# Sensors.net
KiCad netlist of a schematic drawn in Altium Designer
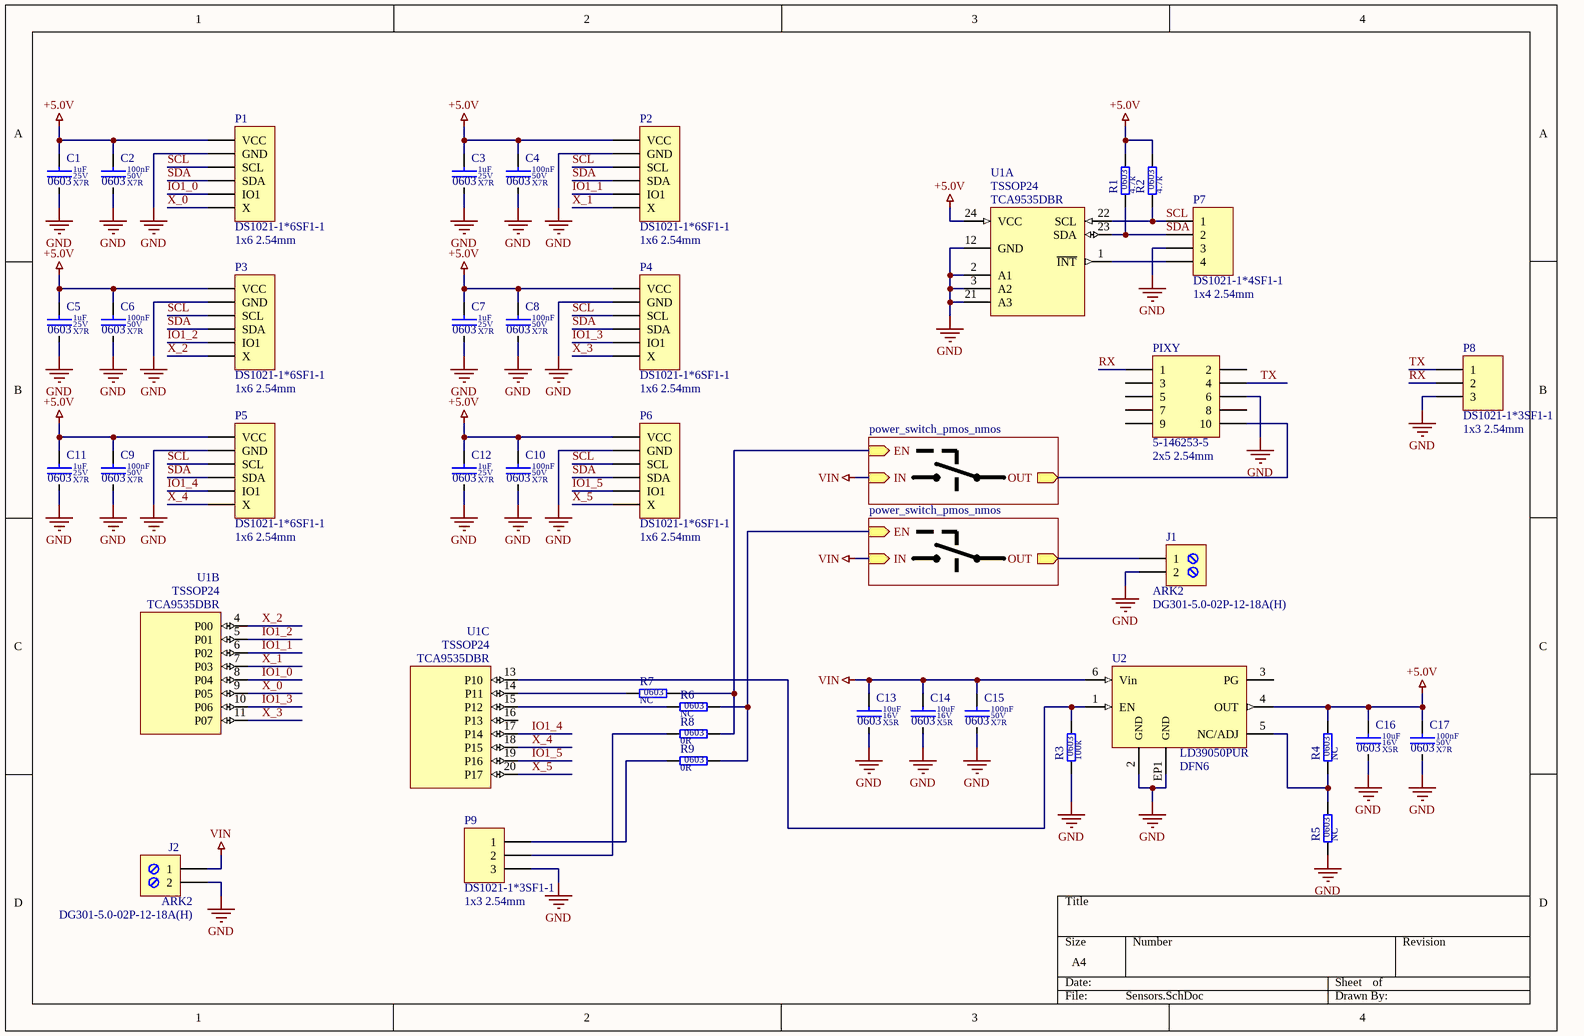
[diagram p0: Sensors.SchDoc]

(export (version "E")
  (design (tool "Eeschema 10.0.6"))
  (components
    (comp (ref "C1")
      (value "1uF")
      (footprint "C_0603_1608")
      (description "Capacitor")
      (fields
        (field (name "DIELECTRIC") "X7R")
        (field (name "VOLTAGE") "25V")
        (field (name "SCH_FOOTPRINT") "0603")
        (field (name "PART NUMBER") "C_1uF_25V_X7R_0603_10")
        (field (name "MANUFACTURER") "Samsung")
      )
      (libsource (lib "Library") (part "C"))
    )
    (comp (ref "C2")
      (value "100nF")
      (footprint "C_0603_1608")
      (description "Capacitor")
      (fields
        (field (name "DIELECTRIC") "X7R")
        (field (name "VOLTAGE") "50V")
        (field (name "SCH_FOOTPRINT") "0603")
        (field (name "PART NUMBER") "C_100nF_50V_X7R_0603_5")
        (field (name "MANUFACTURER") "Samsung")
      )
      (libsource (lib "Library") (part "C"))
    )
    (comp (ref "C3")
      (value "1uF")
      (footprint "C_0603_1608")
      (description "Capacitor")
      (fields
        (field (name "DIELECTRIC") "X7R")
        (field (name "VOLTAGE") "25V")
        (field (name "SCH_FOOTPRINT") "0603")
        (field (name "PART NUMBER") "C_1uF_25V_X7R_0603_10")
        (field (name "MANUFACTURER") "Samsung")
      )
      (libsource (lib "Library") (part "C"))
    )
    (comp (ref "C4")
      (value "100nF")
      (footprint "C_0603_1608")
      (description "Capacitor")
      (fields
        (field (name "DIELECTRIC") "X7R")
        (field (name "VOLTAGE") "50V")
        (field (name "SCH_FOOTPRINT") "0603")
        (field (name "PART NUMBER") "C_100nF_50V_X7R_0603_5")
        (field (name "MANUFACTURER") "Samsung")
      )
      (libsource (lib "Library") (part "C"))
    )
    (comp (ref "C5")
      (value "1uF")
      (footprint "C_0603_1608")
      (description "Capacitor")
      (fields
        (field (name "DIELECTRIC") "X7R")
        (field (name "VOLTAGE") "25V")
        (field (name "SCH_FOOTPRINT") "0603")
        (field (name "PART NUMBER") "C_1uF_25V_X7R_0603_10")
        (field (name "MANUFACTURER") "Samsung")
      )
      (libsource (lib "Library") (part "C"))
    )
    (comp (ref "C6")
      (value "100nF")
      (footprint "C_0603_1608")
      (description "Capacitor")
      (fields
        (field (name "DIELECTRIC") "X7R")
        (field (name "VOLTAGE") "50V")
        (field (name "SCH_FOOTPRINT") "0603")
        (field (name "PART NUMBER") "C_100nF_50V_X7R_0603_5")
        (field (name "MANUFACTURER") "Samsung")
      )
      (libsource (lib "Library") (part "C"))
    )
    (comp (ref "C7")
      (value "1uF")
      (footprint "C_0603_1608")
      (description "Capacitor")
      (fields
        (field (name "DIELECTRIC") "X7R")
        (field (name "VOLTAGE") "25V")
        (field (name "SCH_FOOTPRINT") "0603")
        (field (name "PART NUMBER") "C_1uF_25V_X7R_0603_10")
        (field (name "MANUFACTURER") "Samsung")
      )
      (libsource (lib "Library") (part "C"))
    )
    (comp (ref "C8")
      (value "100nF")
      (footprint "C_0603_1608")
      (description "Capacitor")
      (fields
        (field (name "DIELECTRIC") "X7R")
        (field (name "VOLTAGE") "50V")
        (field (name "SCH_FOOTPRINT") "0603")
        (field (name "PART NUMBER") "C_100nF_50V_X7R_0603_5")
        (field (name "MANUFACTURER") "Samsung")
      )
      (libsource (lib "Library") (part "C"))
    )
    (comp (ref "C9")
      (value "100nF")
      (footprint "C_0603_1608")
      (description "Capacitor")
      (fields
        (field (name "DIELECTRIC") "X7R")
        (field (name "VOLTAGE") "50V")
        (field (name "SCH_FOOTPRINT") "0603")
        (field (name "PART NUMBER") "C_100nF_50V_X7R_0603_5")
        (field (name "MANUFACTURER") "Samsung")
      )
      (libsource (lib "Library") (part "C"))
    )
    (comp (ref "C10")
      (value "100nF")
      (footprint "C_0603_1608")
      (description "Capacitor")
      (fields
        (field (name "DIELECTRIC") "X7R")
        (field (name "VOLTAGE") "50V")
        (field (name "SCH_FOOTPRINT") "0603")
        (field (name "PART NUMBER") "C_100nF_50V_X7R_0603_5")
        (field (name "MANUFACTURER") "Samsung")
      )
      (libsource (lib "Library") (part "C"))
    )
    (comp (ref "C11")
      (value "1uF")
      (footprint "C_0603_1608")
      (description "Capacitor")
      (fields
        (field (name "DIELECTRIC") "X7R")
        (field (name "VOLTAGE") "25V")
        (field (name "SCH_FOOTPRINT") "0603")
        (field (name "PART NUMBER") "C_1uF_25V_X7R_0603_10")
        (field (name "MANUFACTURER") "Samsung")
      )
      (libsource (lib "Library") (part "C"))
    )
    (comp (ref "C12")
      (value "1uF")
      (footprint "C_0603_1608")
      (description "Capacitor")
      (fields
        (field (name "DIELECTRIC") "X7R")
        (field (name "VOLTAGE") "25V")
        (field (name "SCH_FOOTPRINT") "0603")
        (field (name "PART NUMBER") "C_1uF_25V_X7R_0603_10")
        (field (name "MANUFACTURER") "Samsung")
      )
      (libsource (lib "Library") (part "C"))
    )
    (comp (ref "C13")
      (value "10uF")
      (footprint "C_0603_1608")
      (description "Capacitor")
      (fields
        (field (name "DIELECTRIC") "X5R")
        (field (name "VOLTAGE") "16V")
        (field (name "SCH_FOOTPRINT") "0603")
        (field (name "PART NUMBER") "C_10uF_16V_X5R_0603_20")
        (field (name "MANUFACTURER") "Samsung Electro-Mechanics")
      )
      (libsource (lib "Library") (part "C"))
    )
    (comp (ref "C14")
      (value "10uF")
      (footprint "C_0603_1608")
      (description "Capacitor")
      (fields
        (field (name "DIELECTRIC") "X5R")
        (field (name "VOLTAGE") "16V")
        (field (name "SCH_FOOTPRINT") "0603")
        (field (name "PART NUMBER") "C_10uF_16V_X5R_0603_20")
        (field (name "MANUFACTURER") "Samsung Electro-Mechanics")
      )
      (libsource (lib "Library") (part "C"))
    )
    (comp (ref "C15")
      (value "100nF")
      (footprint "C_0603_1608")
      (description "Capacitor")
      (fields
        (field (name "DIELECTRIC") "X7R")
        (field (name "VOLTAGE") "50V")
        (field (name "SCH_FOOTPRINT") "0603")
        (field (name "PART NUMBER") "C_100nF_50V_X7R_0603_5")
        (field (name "MANUFACTURER") "Samsung")
      )
      (libsource (lib "Library") (part "C"))
    )
    (comp (ref "C16")
      (value "10uF")
      (footprint "C_0603_1608")
      (description "Capacitor")
      (fields
        (field (name "DIELECTRIC") "X5R")
        (field (name "VOLTAGE") "16V")
        (field (name "SCH_FOOTPRINT") "0603")
        (field (name "PART NUMBER") "C_10uF_16V_X5R_0603_20")
        (field (name "MANUFACTURER") "Samsung Electro-Mechanics")
      )
      (libsource (lib "Library") (part "C"))
    )
    (comp (ref "C17")
      (value "100nF")
      (footprint "C_0603_1608")
      (description "Capacitor")
      (fields
        (field (name "DIELECTRIC") "X7R")
        (field (name "VOLTAGE") "50V")
        (field (name "SCH_FOOTPRINT") "0603")
        (field (name "PART NUMBER") "C_100nF_50V_X7R_0603_5")
        (field (name "MANUFACTURER") "Samsung")
      )
      (libsource (lib "Library") (part "C"))
    )
    (comp (ref "J1")
      (value "DG301-5.0-02P-12-18A(H)")
      (footprint "J_ARK2")
      (description "ARK Screw terminal, 2-Pin")
      (fields
        (field (name "SCH_FOOTPRINT") "ARK2")
        (field (name "PART NUMBER") "J_TB-5.0-P-2P")
        (field (name "MANUFACTURER") "DEGSON ELECTRONICS")
      )
      (libsource (lib "") (part "J_ARK2_1"))
    )
    (comp (ref "J2")
      (value "DG301-5.0-02P-12-18A(H)")
      (footprint "J_ARK2")
      (description "ARK Screw terminal, 2-Pin")
      (fields
        (field (name "SCH_FOOTPRINT") "ARK2")
        (field (name "PART NUMBER") "J_TB-5.0-P-2P")
        (field (name "MANUFACTURER") "DEGSON ELECTRONICS")
      )
      (libsource (lib "Library") (part "J_ARK2"))
    )
    (comp (ref "P1")
      (value "DS1021-1*6SF1-1")
      (footprint "P_HEADER_1x6_2.54")
      (description "Header, 6-Pin")
      (fields
        (field (name "PART NUMBER") "P_HEADER_1x6_2.54")
        (field (name "SCH_FOOTPRINT") "1x6 2.54mm")
        (field (name "MANUFACTURER") "Connfly")
      )
      (libsource (lib "Library") (part "P_HEADER_1x6"))
    )
    (comp (ref "P2")
      (value "DS1021-1*6SF1-1")
      (footprint "P_HEADER_1x6_2.54")
      (description "Header, 6-Pin")
      (fields
        (field (name "PART NUMBER") "P_HEADER_1x6_2.54")
        (field (name "SCH_FOOTPRINT") "1x6 2.54mm")
        (field (name "MANUFACTURER") "Connfly")
      )
      (libsource (lib "Library") (part "P_HEADER_1x6"))
    )
    (comp (ref "P3")
      (value "DS1021-1*6SF1-1")
      (footprint "P_HEADER_1x6_2.54")
      (description "Header, 6-Pin")
      (fields
        (field (name "PART NUMBER") "P_HEADER_1x6_2.54")
        (field (name "SCH_FOOTPRINT") "1x6 2.54mm")
        (field (name "MANUFACTURER") "Connfly")
      )
      (libsource (lib "Library") (part "P_HEADER_1x6"))
    )
    (comp (ref "P4")
      (value "DS1021-1*6SF1-1")
      (footprint "P_HEADER_1x6_2.54")
      (description "Header, 6-Pin")
      (fields
        (field (name "PART NUMBER") "P_HEADER_1x6_2.54")
        (field (name "SCH_FOOTPRINT") "1x6 2.54mm")
        (field (name "MANUFACTURER") "Connfly")
      )
      (libsource (lib "Library") (part "P_HEADER_1x6"))
    )
    (comp (ref "P5")
      (value "DS1021-1*6SF1-1")
      (footprint "P_HEADER_1x6_2.54")
      (description "Header, 6-Pin")
      (fields
        (field (name "PART NUMBER") "P_HEADER_1x6_2.54")
        (field (name "SCH_FOOTPRINT") "1x6 2.54mm")
        (field (name "MANUFACTURER") "Connfly")
      )
      (libsource (lib "Library") (part "P_HEADER_1x6"))
    )
    (comp (ref "P6")
      (value "DS1021-1*6SF1-1")
      (footprint "P_HEADER_1x6_2.54")
      (description "Header, 6-Pin")
      (fields
        (field (name "PART NUMBER") "P_HEADER_1x6_2.54")
        (field (name "SCH_FOOTPRINT") "1x6 2.54mm")
        (field (name "MANUFACTURER") "Connfly")
      )
      (libsource (lib "Library") (part "P_HEADER_1x6"))
    )
    (comp (ref "P7")
      (value "DS1021-1*4SF1-1")
      (footprint "P_HEADER_1x4_2.54")
      (description "Header, 4-Pin")
      (fields
        (field (name "PART NUMBER") "P_HEADER_1x4_2.54")
        (field (name "SCH_FOOTPRINT") "1x4 2.54mm")
        (field (name "MANUFACTURER") "Connfly")
      )
      (libsource (lib "Library") (part "P_HEADER_1x4"))
    )
    (comp (ref "P8")
      (value "DS1021-1*3SF1-1")
      (footprint "P_HEADER_1x3_2.54")
      (description "Header, 3-Pin")
      (fields
        (field (name "PART NUMBER") "P_HEADER_1x3_2.54")
        (field (name "SCH_FOOTPRINT") "1x3 2.54mm")
        (field (name "MANUFACTURER") "Connfly")
      )
      (libsource (lib "") (part "P_HEADER_1x3_1"))
    )
    (comp (ref "P9")
      (value "DS1021-1*3SF1-1")
      (footprint "P_HEADER_1x3_2.54")
      (description "Header, 3-Pin")
      (fields
        (field (name "PART NUMBER") "P_HEADER_1x3_2.54")
        (field (name "SCH_FOOTPRINT") "1x3 2.54mm")
        (field (name "MANUFACTURER") "Connfly")
      )
      (libsource (lib "Library") (part "P_HEADER_1x3"))
    )
    (comp (ref "PIXY")
      (value "5-146253-5")
      (footprint "P_HEADER_2x5_2.54")
      (description "Header, 10-Pin, Dual row")
      (fields
        (field (name "PART NUMBER") "P_HEADER_2x5_2.54")
        (field (name "SCH_FOOTPRINT") "2x5 2.54mm")
        (field (name "MANUFACTURER") "TE Connectivity")
      )
      (libsource (lib "Library") (part "P_HEADER_2x5"))
    )
    (comp (ref "R1")
      (value "4.7k")
      (footprint "R_0603_1608")
      (fields
        (field (name "SCH_FOOTPRINT") "0603")
        (field (name "PART NUMBER") "R_4.7k_0603_1")
        (field (name "VOLTAGE") "75V")
        (field (name "POWER") "100mW")
      )
      (libsource (lib "Library") (part "R"))
    )
    (comp (ref "R2")
      (value "4.7k")
      (footprint "R_0603_1608")
      (fields
        (field (name "SCH_FOOTPRINT") "0603")
        (field (name "PART NUMBER") "R_4.7k_0603_1")
        (field (name "VOLTAGE") "75V")
        (field (name "POWER") "100mW")
      )
      (libsource (lib "Library") (part "R"))
    )
    (comp (ref "R3")
      (value "100k")
      (footprint "R_0603_1608")
      (fields
        (field (name "SCH_FOOTPRINT") "0603")
        (field (name "PART NUMBER") "R_100k_0603_1")
        (field (name "VOLTAGE") "50V")
        (field (name "POWER") "100mW")
      )
      (libsource (lib "Library") (part "R"))
    )
    (comp (ref "R4")
      (value "NC")
      (footprint "R_NC_0603_1608")
      (fields
        (field (name "SCH_FOOTPRINT") "0603")
        (field (name "PART NUMBER") "R_GENERIC_0603")
        (field (name "Comment") "Resistor")
      )
      (libsource (lib "Library") (part "R"))
    )
    (comp (ref "R5")
      (value "NC")
      (footprint "R_NC_0603_1608")
      (fields
        (field (name "SCH_FOOTPRINT") "0603")
        (field (name "PART NUMBER") "R_GENERIC_0603")
        (field (name "Comment") "Resistor")
      )
      (libsource (lib "Library") (part "R"))
    )
    (comp (ref "R6")
      (value "NC")
      (footprint "R_NC_0603_1608")
      (fields
        (field (name "SCH_FOOTPRINT") "0603")
        (field (name "PART NUMBER") "R_GENERIC_0603")
        (field (name "Comment") "Resistor")
      )
      (libsource (lib "Library") (part "R"))
    )
    (comp (ref "R7")
      (value "NC")
      (footprint "R_NC_0603_1608")
      (fields
        (field (name "SCH_FOOTPRINT") "0603")
        (field (name "PART NUMBER") "R_GENERIC_0603")
        (field (name "Comment") "Resistor")
      )
      (libsource (lib "Library") (part "R"))
    )
    (comp (ref "R8")
      (value "0R")
      (footprint "R_0603_1608")
      (fields
        (field (name "SCH_FOOTPRINT") "0603")
        (field (name "PART NUMBER") "R_0R_0603_5")
        (field (name "VOLTAGE") "50V")
        (field (name "POWER") "100mW")
      )
      (libsource (lib "Library") (part "R"))
    )
    (comp (ref "R9")
      (value "0R")
      (footprint "R_0603_1608")
      (fields
        (field (name "SCH_FOOTPRINT") "0603")
        (field (name "PART NUMBER") "R_0R_0603_5")
        (field (name "VOLTAGE") "50V")
        (field (name "POWER") "100mW")
      )
      (libsource (lib "Library") (part "R"))
    )
    (comp (ref "U1")
      (value "TCA9535DBR")
      (footprint "TSSOP24_8x8")
      (fields
        (field (name "SCH_FOOTPRINT") "TSSOP24")
        (field (name "PART NUMBER") "U_TCA9535DBR")
        (field (name "MANUFACTURER") "Texas Instruments")
      )
      (libsource (lib "Library") (part "U_TCA9535DBX"))
    )
    (comp (ref "U2")
      (value "LD39050PUR")
      (footprint "DFN6_3x3")
      (fields
        (field (name "SCH_FOOTPRINT") "DFN6")
        (field (name "PART NUMBER") "VL_LD39050PUR")
        (field (name "VOLTAGE") "ADJ")
        (field (name "MANUFACTURER") "STMicroelectronics")
      )
      (libsource (lib "Library") (part "VL_LD39050"))
    )
  )
  (nets
    (net (code "1") (name "+5.0V") (class "Default")
      (node (ref "C1") (pin "1") (pinfunction "1_1") (pintype "passive"))
      (node (ref "C10") (pin "1") (pinfunction "1_1") (pintype "passive"))
      (node (ref "C11") (pin "1") (pinfunction "1_1") (pintype "passive"))
      (node (ref "C12") (pin "1") (pinfunction "1_1") (pintype "passive"))
      (node (ref "C16") (pin "1") (pinfunction "1_1") (pintype "passive"))
      (node (ref "C17") (pin "1") (pinfunction "1_1") (pintype "passive"))
      (node (ref "C2") (pin "1") (pinfunction "1_1") (pintype "passive"))
      (node (ref "C3") (pin "1") (pinfunction "1_1") (pintype "passive"))
      (node (ref "C4") (pin "1") (pinfunction "1_1") (pintype "passive"))
      (node (ref "C5") (pin "1") (pinfunction "1_1") (pintype "passive"))
      (node (ref "C6") (pin "1") (pinfunction "1_1") (pintype "passive"))
      (node (ref "C7") (pin "1") (pinfunction "1_1") (pintype "passive"))
      (node (ref "C8") (pin "1") (pinfunction "1_1") (pintype "passive"))
      (node (ref "C9") (pin "1") (pinfunction "1_1") (pintype "passive"))
      (node (ref "P1") (pin "1") (pinfunction "VCC_1") (pintype "passive"))
      (node (ref "P2") (pin "1") (pinfunction "VCC_1") (pintype "passive"))
      (node (ref "P3") (pin "1") (pinfunction "VCC_1") (pintype "passive"))
      (node (ref "P4") (pin "1") (pinfunction "VCC_1") (pintype "passive"))
      (node (ref "P5") (pin "1") (pinfunction "VCC_1") (pintype "passive"))
      (node (ref "P6") (pin "1") (pinfunction "VCC_1") (pintype "passive"))
      (node (ref "R1") (pin "2") (pinfunction "2_2") (pintype "passive"))
      (node (ref "R2") (pin "2") (pinfunction "2_2") (pintype "passive"))
      (node (ref "R4") (pin "2") (pinfunction "2_2") (pintype "passive"))
      (node (ref "U1") (pin "24") (pinfunction "VCC_24") (pintype "input"))
      (node (ref "U2") (pin "4") (pinfunction "OUT_4") (pintype "output"))
    )
    (net (code "2") (name "/EN") (class "Default")
      (node (ref "R6") (pin "2") (pinfunction "2_2") (pintype "passive"))
      (node (ref "R9") (pin "2") (pinfunction "2_2") (pintype "passive"))
    )
    (net (code "3") (name "/EN_1") (class "Default")
      (node (ref "R7") (pin "2") (pinfunction "2_2") (pintype "passive"))
      (node (ref "R8") (pin "2") (pinfunction "2_2") (pintype "passive"))
    )
    (net (code "4") (name "/IO1_0") (class "Default")
      (node (ref "P1") (pin "5") (pinfunction "IO1_5") (pintype "passive"))
      (node (ref "U1") (pin "8") (pinfunction "P04_8") (pintype "bidirectional"))
    )
    (net (code "5") (name "/IO1_1") (class "Default")
      (node (ref "P2") (pin "5") (pinfunction "IO1_5") (pintype "passive"))
      (node (ref "U1") (pin "6") (pinfunction "P02_6") (pintype "bidirectional"))
    )
    (net (code "6") (name "/IO1_2") (class "Default")
      (node (ref "P3") (pin "5") (pinfunction "IO1_5") (pintype "passive"))
      (node (ref "U1") (pin "5") (pinfunction "P01_5") (pintype "bidirectional"))
    )
    (net (code "7") (name "/IO1_3") (class "Default")
      (node (ref "P4") (pin "5") (pinfunction "IO1_5") (pintype "passive"))
      (node (ref "U1") (pin "10") (pinfunction "P06_10") (pintype "bidirectional"))
    )
    (net (code "8") (name "/IO1_4") (class "Default")
      (node (ref "P5") (pin "5") (pinfunction "IO1_5") (pintype "passive"))
      (node (ref "U1") (pin "17") (pinfunction "P14_17") (pintype "bidirectional"))
    )
    (net (code "9") (name "/IO1_5") (class "Default")
      (node (ref "P6") (pin "5") (pinfunction "IO1_5") (pintype "passive"))
      (node (ref "U1") (pin "19") (pinfunction "P16_19") (pintype "bidirectional"))
    )
    (net (code "10") (name "/OUT") (class "Default")
      (node (ref "J1") (pin "1") (pinfunction "1_1") (pintype "passive"))
    )
    (net (code "11") (name "/OUT_1") (class "Default")
      (node (ref "PIXY") (pin "10") (pinfunction "10_10") (pintype "passive"))
    )
    (net (code "12") (name "/RX") (class "Default")
      (node (ref "P8") (pin "2") (pinfunction "2_2") (pintype "passive"))
      (node (ref "PIXY") (pin "1") (pinfunction "1_1") (pintype "passive"))
    )
    (net (code "13") (name "/SCL") (class "Default")
      (node (ref "P1") (pin "3") (pinfunction "SCL_3") (pintype "passive"))
      (node (ref "P2") (pin "3") (pinfunction "SCL_3") (pintype "passive"))
      (node (ref "P3") (pin "3") (pinfunction "SCL_3") (pintype "passive"))
      (node (ref "P4") (pin "3") (pinfunction "SCL_3") (pintype "passive"))
      (node (ref "P5") (pin "3") (pinfunction "SCL_3") (pintype "passive"))
      (node (ref "P6") (pin "3") (pinfunction "SCL_3") (pintype "passive"))
      (node (ref "P7") (pin "1") (pinfunction "1_1") (pintype "passive"))
      (node (ref "R2") (pin "1") (pinfunction "1_1") (pintype "passive"))
      (node (ref "U1") (pin "22") (pinfunction "SCL_22") (pintype "input"))
    )
    (net (code "14") (name "/SDA") (class "Default")
      (node (ref "P1") (pin "4") (pinfunction "SDA_4") (pintype "passive"))
      (node (ref "P2") (pin "4") (pinfunction "SDA_4") (pintype "passive"))
      (node (ref "P3") (pin "4") (pinfunction "SDA_4") (pintype "passive"))
      (node (ref "P4") (pin "4") (pinfunction "SDA_4") (pintype "passive"))
      (node (ref "P5") (pin "4") (pinfunction "SDA_4") (pintype "passive"))
      (node (ref "P6") (pin "4") (pinfunction "SDA_4") (pintype "passive"))
      (node (ref "P7") (pin "2") (pinfunction "2_2") (pintype "passive"))
      (node (ref "R1") (pin "1") (pinfunction "1_1") (pintype "passive"))
      (node (ref "U1") (pin "23") (pinfunction "SDA_23") (pintype "bidirectional"))
    )
    (net (code "15") (name "/TX") (class "Default")
      (node (ref "P8") (pin "1") (pinfunction "1_1") (pintype "passive"))
      (node (ref "PIXY") (pin "4") (pinfunction "4_4") (pintype "passive"))
    )
    (net (code "16") (name "/X_0") (class "Default")
      (node (ref "P1") (pin "6") (pinfunction "X_6") (pintype "passive"))
      (node (ref "U1") (pin "9") (pinfunction "P05_9") (pintype "bidirectional"))
    )
    (net (code "17") (name "/X_1") (class "Default")
      (node (ref "P2") (pin "6") (pinfunction "X_6") (pintype "passive"))
      (node (ref "U1") (pin "7") (pinfunction "P03_7") (pintype "bidirectional"))
    )
    (net (code "18") (name "/X_2") (class "Default")
      (node (ref "P3") (pin "6") (pinfunction "X_6") (pintype "passive"))
      (node (ref "U1") (pin "4") (pinfunction "P00_4") (pintype "bidirectional"))
    )
    (net (code "19") (name "/X_3") (class "Default")
      (node (ref "P4") (pin "6") (pinfunction "X_6") (pintype "passive"))
      (node (ref "U1") (pin "11") (pinfunction "P07_11") (pintype "bidirectional"))
    )
    (net (code "20") (name "/X_4") (class "Default")
      (node (ref "P5") (pin "6") (pinfunction "X_6") (pintype "passive"))
      (node (ref "U1") (pin "18") (pinfunction "P15_18") (pintype "bidirectional"))
    )
    (net (code "21") (name "/X_5") (class "Default")
      (node (ref "P6") (pin "6") (pinfunction "X_6") (pintype "passive"))
      (node (ref "U1") (pin "20") (pinfunction "P17_20") (pintype "bidirectional"))
    )
    (net (code "22") (name "GND") (class "Default")
      (node (ref "C1") (pin "2") (pinfunction "2_2") (pintype "passive"))
      (node (ref "C10") (pin "2") (pinfunction "2_2") (pintype "passive"))
      (node (ref "C11") (pin "2") (pinfunction "2_2") (pintype "passive"))
      (node (ref "C12") (pin "2") (pinfunction "2_2") (pintype "passive"))
      (node (ref "C13") (pin "2") (pinfunction "2_2") (pintype "passive"))
      (node (ref "C14") (pin "2") (pinfunction "2_2") (pintype "passive"))
      (node (ref "C15") (pin "2") (pinfunction "2_2") (pintype "passive"))
      (node (ref "C16") (pin "2") (pinfunction "2_2") (pintype "passive"))
      (node (ref "C17") (pin "2") (pinfunction "2_2") (pintype "passive"))
      (node (ref "C2") (pin "2") (pinfunction "2_2") (pintype "passive"))
      (node (ref "C3") (pin "2") (pinfunction "2_2") (pintype "passive"))
      (node (ref "C4") (pin "2") (pinfunction "2_2") (pintype "passive"))
      (node (ref "C5") (pin "2") (pinfunction "2_2") (pintype "passive"))
      (node (ref "C6") (pin "2") (pinfunction "2_2") (pintype "passive"))
      (node (ref "C7") (pin "2") (pinfunction "2_2") (pintype "passive"))
      (node (ref "C8") (pin "2") (pinfunction "2_2") (pintype "passive"))
      (node (ref "C9") (pin "2") (pinfunction "2_2") (pintype "passive"))
      (node (ref "J1") (pin "2") (pinfunction "2_2") (pintype "passive"))
      (node (ref "J2") (pin "2") (pinfunction "2_2") (pintype "passive"))
      (node (ref "P1") (pin "2") (pinfunction "GND_2") (pintype "passive"))
      (node (ref "P2") (pin "2") (pinfunction "GND_2") (pintype "passive"))
      (node (ref "P3") (pin "2") (pinfunction "GND_2") (pintype "passive"))
      (node (ref "P4") (pin "2") (pinfunction "GND_2") (pintype "passive"))
      (node (ref "P5") (pin "2") (pinfunction "GND_2") (pintype "passive"))
      (node (ref "P6") (pin "2") (pinfunction "GND_2") (pintype "passive"))
      (node (ref "P7") (pin "3") (pinfunction "3_3") (pintype "passive"))
      (node (ref "P8") (pin "3") (pinfunction "3_3") (pintype "passive"))
      (node (ref "P9") (pin "3") (pinfunction "3_3") (pintype "passive"))
      (node (ref "PIXY") (pin "6") (pinfunction "6_6") (pintype "passive"))
      (node (ref "R3") (pin "1") (pinfunction "1_1") (pintype "passive"))
      (node (ref "R5") (pin "1") (pinfunction "1_1") (pintype "passive"))
      (node (ref "U1") (pin "12") (pinfunction "GND_12") (pintype "power_in"))
      (node (ref "U1") (pin "2") (pinfunction "A1_2") (pintype "passive"))
      (node (ref "U1") (pin "21") (pinfunction "A3_21") (pintype "passive"))
      (node (ref "U1") (pin "3") (pinfunction "A2_3") (pintype "passive"))
      (node (ref "U2") (pin "2") (pinfunction "GND_2") (pintype "power_in"))
      (node (ref "U2") (pin "EP1") (pinfunction "GND_EP1") (pintype "power_in"))
    )
    (net (code "23") (name "Net-(P9-Pad1)") (class "Default")
      (node (ref "P9") (pin "1") (pinfunction "1_1") (pintype "passive"))
      (node (ref "R9") (pin "1") (pinfunction "1_1") (pintype "passive"))
    )
    (net (code "24") (name "Net-(P9-Pad2)") (class "Default")
      (node (ref "P9") (pin "2") (pinfunction "2_2") (pintype "passive"))
      (node (ref "R8") (pin "1") (pinfunction "1_1") (pintype "passive"))
    )
    (net (code "25") (name "Net-(U1A-~{INT})") (class "Default")
      (node (ref "P7") (pin "4") (pinfunction "4_4") (pintype "passive"))
      (node (ref "U1") (pin "1") (pinfunction "~{INT}_1") (pintype "output"))
    )
    (net (code "26") (name "Net-(U1C-P10)") (class "Default")
      (node (ref "R3") (pin "2") (pinfunction "2_2") (pintype "passive"))
      (node (ref "U1") (pin "13") (pinfunction "P10_13") (pintype "bidirectional"))
      (node (ref "U2") (pin "1") (pinfunction "EN_1") (pintype "input"))
    )
    (net (code "27") (name "Net-(U1C-P11)") (class "Default")
      (node (ref "R7") (pin "1") (pinfunction "1_1") (pintype "passive"))
      (node (ref "U1") (pin "14") (pinfunction "P11_14") (pintype "bidirectional"))
    )
    (net (code "28") (name "Net-(U1C-P12)") (class "Default")
      (node (ref "R6") (pin "1") (pinfunction "1_1") (pintype "passive"))
      (node (ref "U1") (pin "15") (pinfunction "P12_15") (pintype "bidirectional"))
    )
    (net (code "29") (name "Net-(U2-NC{slash}ADJ)") (class "Default")
      (node (ref "R4") (pin "1") (pinfunction "1_1") (pintype "passive"))
      (node (ref "R5") (pin "2") (pinfunction "2_2") (pintype "passive"))
      (node (ref "U2") (pin "5") (pinfunction "NC/ADJ_5") (pintype "passive"))
    )
    (net (code "30") (name "VIN") (class "Default")
      (node (ref "C13") (pin "1") (pinfunction "1_1") (pintype "passive"))
      (node (ref "C14") (pin "1") (pinfunction "1_1") (pintype "passive"))
      (node (ref "C15") (pin "1") (pinfunction "1_1") (pintype "passive"))
      (node (ref "J2") (pin "1") (pinfunction "1_1") (pintype "passive"))
      (node (ref "U2") (pin "6") (pinfunction "Vin_6") (pintype "input"))
    )
    (net (code "31") (name "unconnected-(PIXY-Pad2)") (class "Default")
      (node (ref "PIXY") (pin "2") (pinfunction "2_2") (pintype "passive"))
    )
    (net (code "32") (name "unconnected-(PIXY-Pad3)") (class "Default")
      (node (ref "PIXY") (pin "3") (pinfunction "3_3") (pintype "passive"))
    )
    (net (code "33") (name "unconnected-(PIXY-Pad5)") (class "Default")
      (node (ref "PIXY") (pin "5") (pinfunction "5_5") (pintype "passive"))
    )
    (net (code "34") (name "unconnected-(PIXY-Pad7)") (class "Default")
      (node (ref "PIXY") (pin "7") (pinfunction "7_7") (pintype "passive"))
    )
    (net (code "35") (name "unconnected-(PIXY-Pad8)") (class "Default")
      (node (ref "PIXY") (pin "8") (pinfunction "8_8") (pintype "passive"))
    )
    (net (code "36") (name "unconnected-(PIXY-Pad9)") (class "Default")
      (node (ref "PIXY") (pin "9") (pinfunction "9_9") (pintype "passive"))
    )
    (net (code "37") (name "unconnected-(U1C-P13-Pad16)") (class "Default")
      (node (ref "U1") (pin "16") (pinfunction "P13_16") (pintype "bidirectional"))
    )
    (net (code "38") (name "unconnected-(U2-PG-Pad3)") (class "Default")
      (node (ref "U2") (pin "3") (pinfunction "PG_3") (pintype "passive"))
    )
  )
)
